# mainboard_teensy41.net
KiCad netlist of a schematic drawn in EAGLE
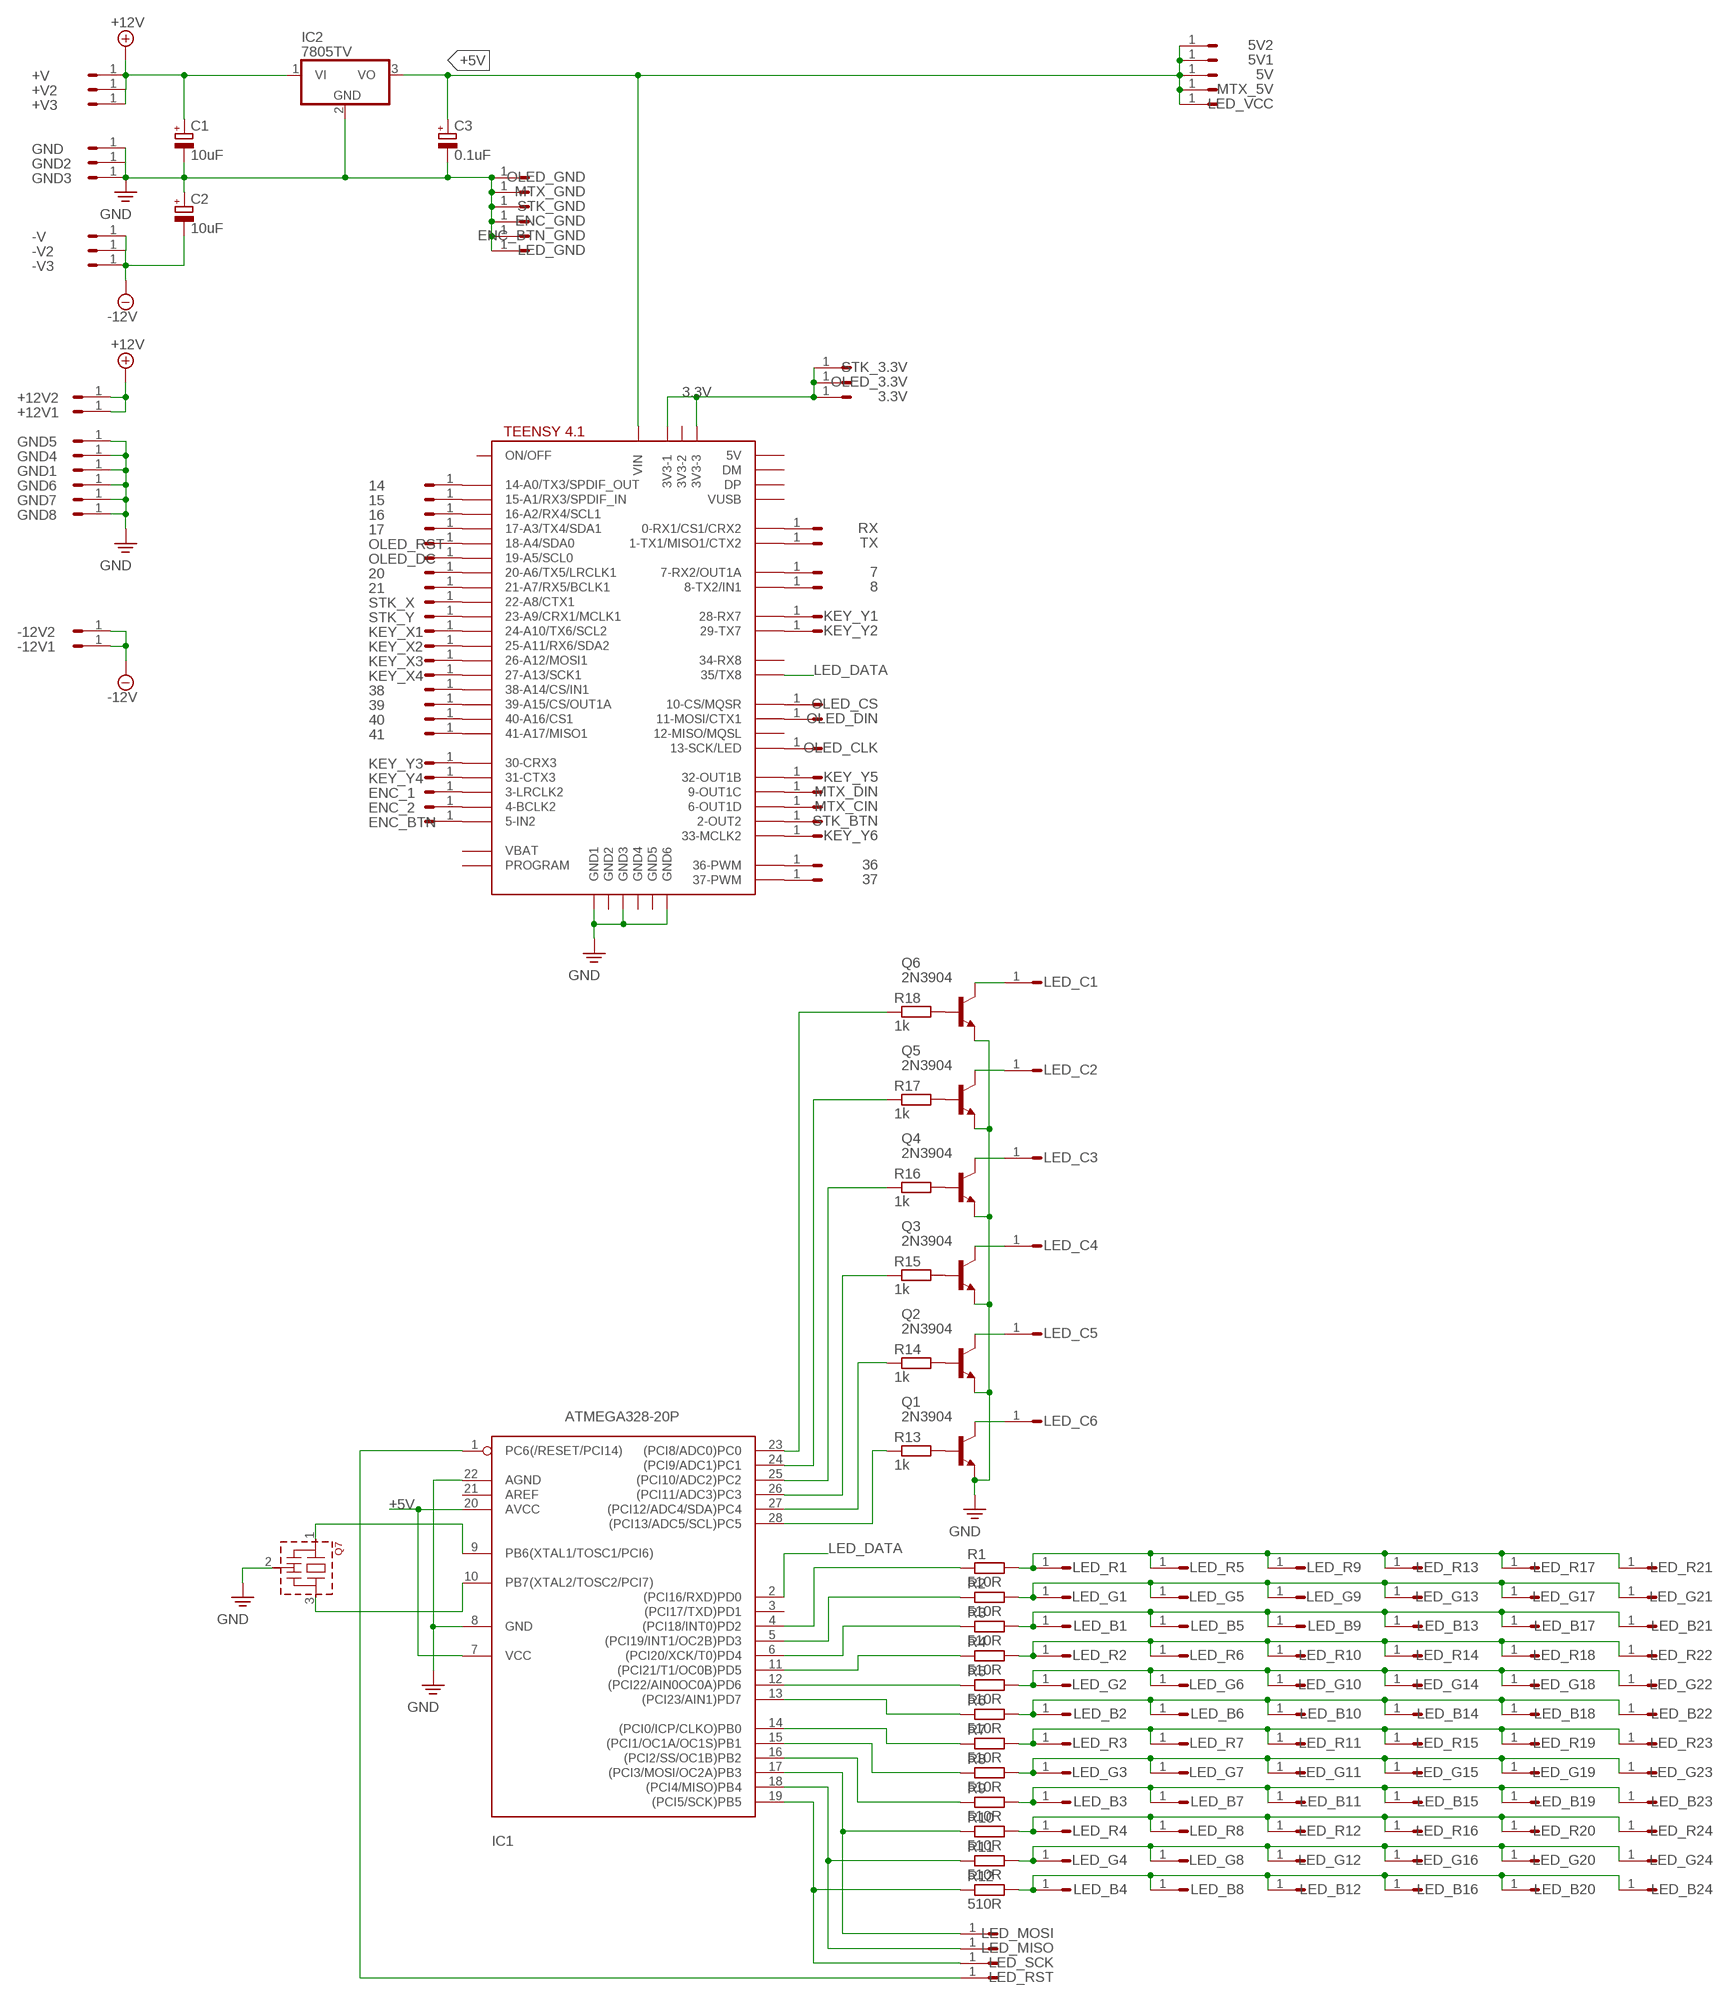
[diagram p0: schematic, sheet 1]

(export (version "E")
  (design (tool "Eeschema 10.0.6"))
  (components
    (comp (ref "+12V1")
      (value "HEADER/MALE/01")
      (footprint "eagle-import:HEADER_MALE_01")
      (fields (field (name "SPICEPREFIX") "X"))
      (libsource (lib "eagle-import") (part "HEADER/MALE/01"))
    )
    (comp (ref "+12V2")
      (value "HEADER/MALE/01")
      (footprint "eagle-import:HEADER_MALE_01")
      (fields (field (name "SPICEPREFIX") "X"))
      (libsource (lib "eagle-import") (part "HEADER/MALE/01"))
    )
    (comp (ref "+V")
      (value "HEADER/MALE/01")
      (footprint "eagle-import:HEADER_MALE_01")
      (fields (field (name "SPICEPREFIX") "X"))
      (libsource (lib "eagle-import") (part "HEADER/MALE/01"))
    )
    (comp (ref "+V2")
      (value "HEADER/MALE/01")
      (footprint "eagle-import:HEADER_MALE_01")
      (fields (field (name "SPICEPREFIX") "X"))
      (libsource (lib "eagle-import") (part "HEADER/MALE/01"))
    )
    (comp (ref "+V3")
      (value "HEADER/MALE/01")
      (footprint "eagle-import:HEADER_MALE_01")
      (fields (field (name "SPICEPREFIX") "X"))
      (libsource (lib "eagle-import") (part "HEADER/MALE/01"))
    )
    (comp (ref "-12V1")
      (value "HEADER/MALE/01")
      (footprint "eagle-import:HEADER_MALE_01")
      (fields (field (name "SPICEPREFIX") "X"))
      (libsource (lib "eagle-import") (part "HEADER/MALE/01"))
    )
    (comp (ref "-12V2")
      (value "HEADER/MALE/01")
      (footprint "eagle-import:HEADER_MALE_01")
      (fields (field (name "SPICEPREFIX") "X"))
      (libsource (lib "eagle-import") (part "HEADER/MALE/01"))
    )
    (comp (ref "-V")
      (value "HEADER/MALE/01")
      (footprint "eagle-import:HEADER_MALE_01")
      (fields (field (name "SPICEPREFIX") "X"))
      (libsource (lib "eagle-import") (part "HEADER/MALE/01"))
    )
    (comp (ref "-V2")
      (value "HEADER/MALE/01")
      (footprint "eagle-import:HEADER_MALE_01")
      (fields (field (name "SPICEPREFIX") "X"))
      (libsource (lib "eagle-import") (part "HEADER/MALE/01"))
    )
    (comp (ref "-V3")
      (value "HEADER/MALE/01")
      (footprint "eagle-import:HEADER_MALE_01")
      (fields (field (name "SPICEPREFIX") "X"))
      (libsource (lib "eagle-import") (part "HEADER/MALE/01"))
    )
    (comp (ref "3.3V")
      (value "HEADER/MALE/01")
      (footprint "eagle-import:HEADER_MALE_01")
      (fields (field (name "SPICEPREFIX") "X"))
      (libsource (lib "eagle-import") (part "HEADER/MALE/01"))
    )
    (comp (ref "5V")
      (value "HEADER/MALE/01")
      (footprint "eagle-import:HEADER_MALE_01")
      (fields (field (name "SPICEPREFIX") "X"))
      (libsource (lib "eagle-import") (part "HEADER/MALE/01"))
    )
    (comp (ref "5V1")
      (value "HEADER/MALE/01")
      (footprint "eagle-import:HEADER_MALE_01")
      (fields (field (name "SPICEPREFIX") "X"))
      (libsource (lib "eagle-import") (part "HEADER/MALE/01"))
    )
    (comp (ref "5V2")
      (value "HEADER/MALE/01")
      (footprint "eagle-import:HEADER_MALE_01")
      (fields (field (name "SPICEPREFIX") "X"))
      (libsource (lib "eagle-import") (part "HEADER/MALE/01"))
    )
    (comp (ref "7")
      (value "HEADER/MALE/01")
      (footprint "eagle-import:HEADER_MALE_01")
      (fields (field (name "SPICEPREFIX") "X"))
      (libsource (lib "eagle-import") (part "HEADER/MALE/01"))
    )
    (comp (ref "8")
      (value "HEADER/MALE/01")
      (footprint "eagle-import:HEADER_MALE_01")
      (fields (field (name "SPICEPREFIX") "X"))
      (libsource (lib "eagle-import") (part "HEADER/MALE/01"))
    )
    (comp (ref "14")
      (value "HEADER/MALE/01")
      (footprint "eagle-import:HEADER_MALE_01")
      (fields (field (name "SPICEPREFIX") "X"))
      (libsource (lib "eagle-import") (part "HEADER/MALE/01"))
    )
    (comp (ref "15")
      (value "HEADER/MALE/01")
      (footprint "eagle-import:HEADER_MALE_01")
      (fields (field (name "SPICEPREFIX") "X"))
      (libsource (lib "eagle-import") (part "HEADER/MALE/01"))
    )
    (comp (ref "16")
      (value "HEADER/MALE/01")
      (footprint "eagle-import:HEADER_MALE_01")
      (fields (field (name "SPICEPREFIX") "X"))
      (libsource (lib "eagle-import") (part "HEADER/MALE/01"))
    )
    (comp (ref "17")
      (value "HEADER/MALE/01")
      (footprint "eagle-import:HEADER_MALE_01")
      (fields (field (name "SPICEPREFIX") "X"))
      (libsource (lib "eagle-import") (part "HEADER/MALE/01"))
    )
    (comp (ref "20")
      (value "HEADER/MALE/01")
      (footprint "eagle-import:HEADER_MALE_01")
      (fields (field (name "SPICEPREFIX") "X"))
      (libsource (lib "eagle-import") (part "HEADER/MALE/01"))
    )
    (comp (ref "21")
      (value "HEADER/MALE/01")
      (footprint "eagle-import:HEADER_MALE_01")
      (fields (field (name "SPICEPREFIX") "X"))
      (libsource (lib "eagle-import") (part "HEADER/MALE/01"))
    )
    (comp (ref "36")
      (value "HEADER/MALE/01")
      (footprint "eagle-import:HEADER_MALE_01")
      (fields (field (name "SPICEPREFIX") "X"))
      (libsource (lib "eagle-import") (part "HEADER/MALE/01"))
    )
    (comp (ref "37")
      (value "HEADER/MALE/01")
      (footprint "eagle-import:HEADER_MALE_01")
      (fields (field (name "SPICEPREFIX") "X"))
      (libsource (lib "eagle-import") (part "HEADER/MALE/01"))
    )
    (comp (ref "38")
      (value "HEADER/MALE/01")
      (footprint "eagle-import:HEADER_MALE_01")
      (fields (field (name "SPICEPREFIX") "X"))
      (libsource (lib "eagle-import") (part "HEADER/MALE/01"))
    )
    (comp (ref "39")
      (value "HEADER/MALE/01")
      (footprint "eagle-import:HEADER_MALE_01")
      (fields (field (name "SPICEPREFIX") "X"))
      (libsource (lib "eagle-import") (part "HEADER/MALE/01"))
    )
    (comp (ref "40")
      (value "HEADER/MALE/01")
      (footprint "eagle-import:HEADER_MALE_01")
      (fields (field (name "SPICEPREFIX") "X"))
      (libsource (lib "eagle-import") (part "HEADER/MALE/01"))
    )
    (comp (ref "41")
      (value "HEADER/MALE/01")
      (footprint "eagle-import:HEADER_MALE_01")
      (fields (field (name "SPICEPREFIX") "X"))
      (libsource (lib "eagle-import") (part "HEADER/MALE/01"))
    )
    (comp (ref "C1")
      (value "10uF")
      (footprint "eagle-import:E2,5-6")
      (fields (field (name "SPICEPREFIX") "C"))
      (libsource (lib "eagle-import") (part "CAPACITOR/POLARIZEDE2.5-6"))
    )
    (comp (ref "C2")
      (value "10uF")
      (footprint "eagle-import:E2,5-6")
      (fields (field (name "SPICEPREFIX") "C"))
      (libsource (lib "eagle-import") (part "CAPACITOR/POLARIZEDE2.5-6"))
    )
    (comp (ref "C3")
      (value "0.1uF")
      (footprint "eagle-import:E2,5-6")
      (fields (field (name "SPICEPREFIX") "C"))
      (libsource (lib "eagle-import") (part "CAPACITOR/POLARIZEDE2.5-6"))
    )
    (comp (ref "ENC_1")
      (value "HEADER/MALE/01")
      (footprint "eagle-import:HEADER_MALE_01")
      (fields (field (name "SPICEPREFIX") "X"))
      (libsource (lib "eagle-import") (part "HEADER/MALE/01"))
    )
    (comp (ref "ENC_2")
      (value "HEADER/MALE/01")
      (footprint "eagle-import:HEADER_MALE_01")
      (fields (field (name "SPICEPREFIX") "X"))
      (libsource (lib "eagle-import") (part "HEADER/MALE/01"))
    )
    (comp (ref "ENC_BTN")
      (value "HEADER/MALE/01")
      (footprint "eagle-import:HEADER_MALE_01")
      (fields (field (name "SPICEPREFIX") "X"))
      (libsource (lib "eagle-import") (part "HEADER/MALE/01"))
    )
    (comp (ref "ENC_BTN_GND")
      (value "HEADER/MALE/01")
      (footprint "eagle-import:HEADER_MALE_01")
      (fields (field (name "SPICEPREFIX") "X"))
      (libsource (lib "eagle-import") (part "HEADER/MALE/01"))
    )
    (comp (ref "ENC_GND")
      (value "HEADER/MALE/01")
      (footprint "eagle-import:HEADER_MALE_01")
      (fields (field (name "SPICEPREFIX") "X"))
      (libsource (lib "eagle-import") (part "HEADER/MALE/01"))
    )
    (comp (ref "GND")
      (value "HEADER/MALE/01")
      (footprint "eagle-import:HEADER_MALE_01")
      (fields (field (name "SPICEPREFIX") "X"))
      (libsource (lib "eagle-import") (part "HEADER/MALE/01"))
    )
    (comp (ref "GND1")
      (value "HEADER/MALE/01")
      (footprint "eagle-import:HEADER_MALE_01")
      (fields (field (name "SPICEPREFIX") "X"))
      (libsource (lib "eagle-import") (part "HEADER/MALE/01"))
    )
    (comp (ref "GND2")
      (value "HEADER/MALE/01")
      (footprint "eagle-import:HEADER_MALE_01")
      (fields (field (name "SPICEPREFIX") "X"))
      (libsource (lib "eagle-import") (part "HEADER/MALE/01"))
    )
    (comp (ref "GND3")
      (value "HEADER/MALE/01")
      (footprint "eagle-import:HEADER_MALE_01")
      (fields (field (name "SPICEPREFIX") "X"))
      (libsource (lib "eagle-import") (part "HEADER/MALE/01"))
    )
    (comp (ref "GND4")
      (value "HEADER/MALE/01")
      (footprint "eagle-import:HEADER_MALE_01")
      (fields (field (name "SPICEPREFIX") "X"))
      (libsource (lib "eagle-import") (part "HEADER/MALE/01"))
    )
    (comp (ref "GND5")
      (value "HEADER/MALE/01")
      (footprint "eagle-import:HEADER_MALE_01")
      (fields (field (name "SPICEPREFIX") "X"))
      (libsource (lib "eagle-import") (part "HEADER/MALE/01"))
    )
    (comp (ref "GND6")
      (value "HEADER/MALE/01")
      (footprint "eagle-import:HEADER_MALE_01")
      (fields (field (name "SPICEPREFIX") "X"))
      (libsource (lib "eagle-import") (part "HEADER/MALE/01"))
    )
    (comp (ref "GND7")
      (value "HEADER/MALE/01")
      (footprint "eagle-import:HEADER_MALE_01")
      (fields (field (name "SPICEPREFIX") "X"))
      (libsource (lib "eagle-import") (part "HEADER/MALE/01"))
    )
    (comp (ref "GND8")
      (value "HEADER/MALE/01")
      (footprint "eagle-import:HEADER_MALE_01")
      (fields (field (name "SPICEPREFIX") "X"))
      (libsource (lib "eagle-import") (part "HEADER/MALE/01"))
    )
    (comp (ref "IC1")
      (value "ATMEGA328-20P")
      (footprint "eagle-import:DIL28-3")
      (libsource (lib "eagle-import") (part "ATMEGA328P-20"))
    )
    (comp (ref "IC2")
      (value "7805TV")
      (footprint "eagle-import:TO220V")
      (libsource (lib "eagle-import") (part "78TV05"))
    )
    (comp (ref "KEY_X1")
      (value "HEADER/MALE/01")
      (footprint "eagle-import:HEADER_MALE_01")
      (fields (field (name "SPICEPREFIX") "X"))
      (libsource (lib "eagle-import") (part "HEADER/MALE/01"))
    )
    (comp (ref "KEY_X2")
      (value "HEADER/MALE/01")
      (footprint "eagle-import:HEADER_MALE_01")
      (fields (field (name "SPICEPREFIX") "X"))
      (libsource (lib "eagle-import") (part "HEADER/MALE/01"))
    )
    (comp (ref "KEY_X3")
      (value "HEADER/MALE/01")
      (footprint "eagle-import:HEADER_MALE_01")
      (fields (field (name "SPICEPREFIX") "X"))
      (libsource (lib "eagle-import") (part "HEADER/MALE/01"))
    )
    (comp (ref "KEY_X4")
      (value "HEADER/MALE/01")
      (footprint "eagle-import:HEADER_MALE_01")
      (fields (field (name "SPICEPREFIX") "X"))
      (libsource (lib "eagle-import") (part "HEADER/MALE/01"))
    )
    (comp (ref "KEY_Y1")
      (value "HEADER/MALE/01")
      (footprint "eagle-import:HEADER_MALE_01")
      (fields (field (name "SPICEPREFIX") "X"))
      (libsource (lib "eagle-import") (part "HEADER/MALE/01"))
    )
    (comp (ref "KEY_Y2")
      (value "HEADER/MALE/01")
      (footprint "eagle-import:HEADER_MALE_01")
      (fields (field (name "SPICEPREFIX") "X"))
      (libsource (lib "eagle-import") (part "HEADER/MALE/01"))
    )
    (comp (ref "KEY_Y3")
      (value "HEADER/MALE/01")
      (footprint "eagle-import:HEADER_MALE_01")
      (fields (field (name "SPICEPREFIX") "X"))
      (libsource (lib "eagle-import") (part "HEADER/MALE/01"))
    )
    (comp (ref "KEY_Y4")
      (value "HEADER/MALE/01")
      (footprint "eagle-import:HEADER_MALE_01")
      (fields (field (name "SPICEPREFIX") "X"))
      (libsource (lib "eagle-import") (part "HEADER/MALE/01"))
    )
    (comp (ref "KEY_Y5")
      (value "HEADER/MALE/01")
      (footprint "eagle-import:HEADER_MALE_01")
      (fields (field (name "SPICEPREFIX") "X"))
      (libsource (lib "eagle-import") (part "HEADER/MALE/01"))
    )
    (comp (ref "KEY_Y6")
      (value "HEADER/MALE/01")
      (footprint "eagle-import:HEADER_MALE_01")
      (fields (field (name "SPICEPREFIX") "X"))
      (libsource (lib "eagle-import") (part "HEADER/MALE/01"))
    )
    (comp (ref "LED_B1")
      (value "HEADER/MALE/01")
      (footprint "eagle-import:HEADER_MALE_01")
      (fields (field (name "SPICEPREFIX") "X"))
      (libsource (lib "eagle-import") (part "HEADER/MALE/01"))
    )
    (comp (ref "LED_B2")
      (value "HEADER/MALE/01")
      (footprint "eagle-import:HEADER_MALE_01")
      (fields (field (name "SPICEPREFIX") "X"))
      (libsource (lib "eagle-import") (part "HEADER/MALE/01"))
    )
    (comp (ref "LED_B3")
      (value "HEADER/MALE/01")
      (footprint "eagle-import:HEADER_MALE_01")
      (fields (field (name "SPICEPREFIX") "X"))
      (libsource (lib "eagle-import") (part "HEADER/MALE/01"))
    )
    (comp (ref "LED_B4")
      (value "HEADER/MALE/01")
      (footprint "eagle-import:HEADER_MALE_01")
      (fields (field (name "SPICEPREFIX") "X"))
      (libsource (lib "eagle-import") (part "HEADER/MALE/01"))
    )
    (comp (ref "LED_B5")
      (value "HEADER/MALE/01")
      (footprint "eagle-import:HEADER_MALE_01")
      (fields (field (name "SPICEPREFIX") "X"))
      (libsource (lib "eagle-import") (part "HEADER/MALE/01"))
    )
    (comp (ref "LED_B6")
      (value "HEADER/MALE/01")
      (footprint "eagle-import:HEADER_MALE_01")
      (fields (field (name "SPICEPREFIX") "X"))
      (libsource (lib "eagle-import") (part "HEADER/MALE/01"))
    )
    (comp (ref "LED_B7")
      (value "HEADER/MALE/01")
      (footprint "eagle-import:HEADER_MALE_01")
      (fields (field (name "SPICEPREFIX") "X"))
      (libsource (lib "eagle-import") (part "HEADER/MALE/01"))
    )
    (comp (ref "LED_B8")
      (value "HEADER/MALE/01")
      (footprint "eagle-import:HEADER_MALE_01")
      (fields (field (name "SPICEPREFIX") "X"))
      (libsource (lib "eagle-import") (part "HEADER/MALE/01"))
    )
    (comp (ref "LED_B9")
      (value "HEADER/MALE/01")
      (footprint "eagle-import:HEADER_MALE_01")
      (fields (field (name "SPICEPREFIX") "X"))
      (libsource (lib "eagle-import") (part "HEADER/MALE/01"))
    )
    (comp (ref "LED_B10")
      (value "HEADER/MALE/01")
      (footprint "eagle-import:HEADER_MALE_01")
      (fields (field (name "SPICEPREFIX") "X"))
      (libsource (lib "eagle-import") (part "HEADER/MALE/01"))
    )
    (comp (ref "LED_B11")
      (value "HEADER/MALE/01")
      (footprint "eagle-import:HEADER_MALE_01")
      (fields (field (name "SPICEPREFIX") "X"))
      (libsource (lib "eagle-import") (part "HEADER/MALE/01"))
    )
    (comp (ref "LED_B12")
      (value "HEADER/MALE/01")
      (footprint "eagle-import:HEADER_MALE_01")
      (fields (field (name "SPICEPREFIX") "X"))
      (libsource (lib "eagle-import") (part "HEADER/MALE/01"))
    )
    (comp (ref "LED_B13")
      (value "HEADER/MALE/01")
      (footprint "eagle-import:HEADER_MALE_01")
      (fields (field (name "SPICEPREFIX") "X"))
      (libsource (lib "eagle-import") (part "HEADER/MALE/01"))
    )
    (comp (ref "LED_B14")
      (value "HEADER/MALE/01")
      (footprint "eagle-import:HEADER_MALE_01")
      (fields (field (name "SPICEPREFIX") "X"))
      (libsource (lib "eagle-import") (part "HEADER/MALE/01"))
    )
    (comp (ref "LED_B15")
      (value "HEADER/MALE/01")
      (footprint "eagle-import:HEADER_MALE_01")
      (fields (field (name "SPICEPREFIX") "X"))
      (libsource (lib "eagle-import") (part "HEADER/MALE/01"))
    )
    (comp (ref "LED_B16")
      (value "HEADER/MALE/01")
      (footprint "eagle-import:HEADER_MALE_01")
      (fields (field (name "SPICEPREFIX") "X"))
      (libsource (lib "eagle-import") (part "HEADER/MALE/01"))
    )
    (comp (ref "LED_B17")
      (value "HEADER/MALE/01")
      (footprint "eagle-import:HEADER_MALE_01")
      (fields (field (name "SPICEPREFIX") "X"))
      (libsource (lib "eagle-import") (part "HEADER/MALE/01"))
    )
    (comp (ref "LED_B18")
      (value "HEADER/MALE/01")
      (footprint "eagle-import:HEADER_MALE_01")
      (fields (field (name "SPICEPREFIX") "X"))
      (libsource (lib "eagle-import") (part "HEADER/MALE/01"))
    )
    (comp (ref "LED_B19")
      (value "HEADER/MALE/01")
      (footprint "eagle-import:HEADER_MALE_01")
      (fields (field (name "SPICEPREFIX") "X"))
      (libsource (lib "eagle-import") (part "HEADER/MALE/01"))
    )
    (comp (ref "LED_B20")
      (value "HEADER/MALE/01")
      (footprint "eagle-import:HEADER_MALE_01")
      (fields (field (name "SPICEPREFIX") "X"))
      (libsource (lib "eagle-import") (part "HEADER/MALE/01"))
    )
    (comp (ref "LED_B21")
      (value "HEADER/MALE/01")
      (footprint "eagle-import:HEADER_MALE_01")
      (fields (field (name "SPICEPREFIX") "X"))
      (libsource (lib "eagle-import") (part "HEADER/MALE/01"))
    )
    (comp (ref "LED_B22")
      (value "HEADER/MALE/01")
      (footprint "eagle-import:HEADER_MALE_01")
      (fields (field (name "SPICEPREFIX") "X"))
      (libsource (lib "eagle-import") (part "HEADER/MALE/01"))
    )
    (comp (ref "LED_B23")
      (value "HEADER/MALE/01")
      (footprint "eagle-import:HEADER_MALE_01")
      (fields (field (name "SPICEPREFIX") "X"))
      (libsource (lib "eagle-import") (part "HEADER/MALE/01"))
    )
    (comp (ref "LED_B24")
      (value "HEADER/MALE/01")
      (footprint "eagle-import:HEADER_MALE_01")
      (fields (field (name "SPICEPREFIX") "X"))
      (libsource (lib "eagle-import") (part "HEADER/MALE/01"))
    )
    (comp (ref "LED_C1")
      (value "HEADER/MALE/01")
      (footprint "eagle-import:HEADER_MALE_01")
      (fields (field (name "SPICEPREFIX") "X"))
      (libsource (lib "eagle-import") (part "HEADER/MALE/01"))
    )
    (comp (ref "LED_C2")
      (value "HEADER/MALE/01")
      (footprint "eagle-import:HEADER_MALE_01")
      (fields (field (name "SPICEPREFIX") "X"))
      (libsource (lib "eagle-import") (part "HEADER/MALE/01"))
    )
    (comp (ref "LED_C3")
      (value "HEADER/MALE/01")
      (footprint "eagle-import:HEADER_MALE_01")
      (fields (field (name "SPICEPREFIX") "X"))
      (libsource (lib "eagle-import") (part "HEADER/MALE/01"))
    )
    (comp (ref "LED_C4")
      (value "HEADER/MALE/01")
      (footprint "eagle-import:HEADER_MALE_01")
      (fields (field (name "SPICEPREFIX") "X"))
      (libsource (lib "eagle-import") (part "HEADER/MALE/01"))
    )
    (comp (ref "LED_C5")
      (value "HEADER/MALE/01")
      (footprint "eagle-import:HEADER_MALE_01")
      (fields (field (name "SPICEPREFIX") "X"))
      (libsource (lib "eagle-import") (part "HEADER/MALE/01"))
    )
    (comp (ref "LED_C6")
      (value "HEADER/MALE/01")
      (footprint "eagle-import:HEADER_MALE_01")
      (fields (field (name "SPICEPREFIX") "X"))
      (libsource (lib "eagle-import") (part "HEADER/MALE/01"))
    )
    (comp (ref "LED_G1")
      (value "HEADER/MALE/01")
      (footprint "eagle-import:HEADER_MALE_01")
      (fields (field (name "SPICEPREFIX") "X"))
      (libsource (lib "eagle-import") (part "HEADER/MALE/01"))
    )
    (comp (ref "LED_G2")
      (value "HEADER/MALE/01")
      (footprint "eagle-import:HEADER_MALE_01")
      (fields (field (name "SPICEPREFIX") "X"))
      (libsource (lib "eagle-import") (part "HEADER/MALE/01"))
    )
    (comp (ref "LED_G3")
      (value "HEADER/MALE/01")
      (footprint "eagle-import:HEADER_MALE_01")
      (fields (field (name "SPICEPREFIX") "X"))
      (libsource (lib "eagle-import") (part "HEADER/MALE/01"))
    )
    (comp (ref "LED_G4")
      (value "HEADER/MALE/01")
      (footprint "eagle-import:HEADER_MALE_01")
      (fields (field (name "SPICEPREFIX") "X"))
      (libsource (lib "eagle-import") (part "HEADER/MALE/01"))
    )
    (comp (ref "LED_G5")
      (value "HEADER/MALE/01")
      (footprint "eagle-import:HEADER_MALE_01")
      (fields (field (name "SPICEPREFIX") "X"))
      (libsource (lib "eagle-import") (part "HEADER/MALE/01"))
    )
    (comp (ref "LED_G6")
      (value "HEADER/MALE/01")
      (footprint "eagle-import:HEADER_MALE_01")
      (fields (field (name "SPICEPREFIX") "X"))
      (libsource (lib "eagle-import") (part "HEADER/MALE/01"))
    )
    (comp (ref "LED_G7")
      (value "HEADER/MALE/01")
      (footprint "eagle-import:HEADER_MALE_01")
      (fields (field (name "SPICEPREFIX") "X"))
      (libsource (lib "eagle-import") (part "HEADER/MALE/01"))
    )
    (comp (ref "LED_G8")
      (value "HEADER/MALE/01")
      (footprint "eagle-import:HEADER_MALE_01")
      (fields (field (name "SPICEPREFIX") "X"))
      (libsource (lib "eagle-import") (part "HEADER/MALE/01"))
    )
    (comp (ref "LED_G9")
      (value "HEADER/MALE/01")
      (footprint "eagle-import:HEADER_MALE_01")
      (fields (field (name "SPICEPREFIX") "X"))
      (libsource (lib "eagle-import") (part "HEADER/MALE/01"))
    )
    (comp (ref "LED_G10")
      (value "HEADER/MALE/01")
      (footprint "eagle-import:HEADER_MALE_01")
      (fields (field (name "SPICEPREFIX") "X"))
      (libsource (lib "eagle-import") (part "HEADER/MALE/01"))
    )
    (comp (ref "LED_G11")
      (value "HEADER/MALE/01")
      (footprint "eagle-import:HEADER_MALE_01")
      (fields (field (name "SPICEPREFIX") "X"))
      (libsource (lib "eagle-import") (part "HEADER/MALE/01"))
    )
    (comp (ref "LED_G12")
      (value "HEADER/MALE/01")
      (footprint "eagle-import:HEADER_MALE_01")
      (fields (field (name "SPICEPREFIX") "X"))
      (libsource (lib "eagle-import") (part "HEADER/MALE/01"))
    )
    (comp (ref "LED_G13")
      (value "HEADER/MALE/01")
      (footprint "eagle-import:HEADER_MALE_01")
      (fields (field (name "SPICEPREFIX") "X"))
      (libsource (lib "eagle-import") (part "HEADER/MALE/01"))
    )
    (comp (ref "LED_G14")
      (value "HEADER/MALE/01")
      (footprint "eagle-import:HEADER_MALE_01")
      (fields (field (name "SPICEPREFIX") "X"))
      (libsource (lib "eagle-import") (part "HEADER/MALE/01"))
    )
    (comp (ref "LED_G15")
      (value "HEADER/MALE/01")
      (footprint "eagle-import:HEADER_MALE_01")
      (fields (field (name "SPICEPREFIX") "X"))
      (libsource (lib "eagle-import") (part "HEADER/MALE/01"))
    )
    (comp (ref "LED_G16")
      (value "HEADER/MALE/01")
      (footprint "eagle-import:HEADER_MALE_01")
      (fields (field (name "SPICEPREFIX") "X"))
      (libsource (lib "eagle-import") (part "HEADER/MALE/01"))
    )
    (comp (ref "LED_G17")
      (value "HEADER/MALE/01")
      (footprint "eagle-import:HEADER_MALE_01")
      (fields (field (name "SPICEPREFIX") "X"))
      (libsource (lib "eagle-import") (part "HEADER/MALE/01"))
    )
    (comp (ref "LED_G18")
      (value "HEADER/MALE/01")
      (footprint "eagle-import:HEADER_MALE_01")
      (fields (field (name "SPICEPREFIX") "X"))
      (libsource (lib "eagle-import") (part "HEADER/MALE/01"))
    )
    (comp (ref "LED_G19")
      (value "HEADER/MALE/01")
      (footprint "eagle-import:HEADER_MALE_01")
      (fields (field (name "SPICEPREFIX") "X"))
      (libsource (lib "eagle-import") (part "HEADER/MALE/01"))
    )
    (comp (ref "LED_G20")
      (value "HEADER/MALE/01")
      (footprint "eagle-import:HEADER_MALE_01")
      (fields (field (name "SPICEPREFIX") "X"))
      (libsource (lib "eagle-import") (part "HEADER/MALE/01"))
    )
    (comp (ref "LED_G21")
      (value "HEADER/MALE/01")
      (footprint "eagle-import:HEADER_MALE_01")
      (fields (field (name "SPICEPREFIX") "X"))
      (libsource (lib "eagle-import") (part "HEADER/MALE/01"))
    )
    (comp (ref "LED_G22")
      (value "HEADER/MALE/01")
      (footprint "eagle-import:HEADER_MALE_01")
      (fields (field (name "SPICEPREFIX") "X"))
      (libsource (lib "eagle-import") (part "HEADER/MALE/01"))
    )
    (comp (ref "LED_G23")
      (value "HEADER/MALE/01")
      (footprint "eagle-import:HEADER_MALE_01")
      (fields (field (name "SPICEPREFIX") "X"))
      (libsource (lib "eagle-import") (part "HEADER/MALE/01"))
    )
    (comp (ref "LED_G24")
      (value "HEADER/MALE/01")
      (footprint "eagle-import:HEADER_MALE_01")
      (fields (field (name "SPICEPREFIX") "X"))
      (libsource (lib "eagle-import") (part "HEADER/MALE/01"))
    )
    (comp (ref "LED_GND")
      (value "HEADER/MALE/01")
      (footprint "eagle-import:HEADER_MALE_01")
      (fields (field (name "SPICEPREFIX") "X"))
      (libsource (lib "eagle-import") (part "HEADER/MALE/01"))
    )
    (comp (ref "LED_MISO")
      (value "HEADER/MALE/01")
      (footprint "eagle-import:HEADER_MALE_01")
      (fields (field (name "SPICEPREFIX") "X"))
      (libsource (lib "eagle-import") (part "HEADER/MALE/01"))
    )
    (comp (ref "LED_MOSI")
      (value "HEADER/MALE/01")
      (footprint "eagle-import:HEADER_MALE_01")
      (fields (field (name "SPICEPREFIX") "X"))
      (libsource (lib "eagle-import") (part "HEADER/MALE/01"))
    )
    (comp (ref "LED_R1")
      (value "HEADER/MALE/01")
      (footprint "eagle-import:HEADER_MALE_01")
      (fields (field (name "SPICEPREFIX") "X"))
      (libsource (lib "eagle-import") (part "HEADER/MALE/01"))
    )
    (comp (ref "LED_R2")
      (value "HEADER/MALE/01")
      (footprint "eagle-import:HEADER_MALE_01")
      (fields (field (name "SPICEPREFIX") "X"))
      (libsource (lib "eagle-import") (part "HEADER/MALE/01"))
    )
    (comp (ref "LED_R3")
      (value "HEADER/MALE/01")
      (footprint "eagle-import:HEADER_MALE_01")
      (fields (field (name "SPICEPREFIX") "X"))
      (libsource (lib "eagle-import") (part "HEADER/MALE/01"))
    )
    (comp (ref "LED_R4")
      (value "HEADER/MALE/01")
      (footprint "eagle-import:HEADER_MALE_01")
      (fields (field (name "SPICEPREFIX") "X"))
      (libsource (lib "eagle-import") (part "HEADER/MALE/01"))
    )
    (comp (ref "LED_R5")
      (value "HEADER/MALE/01")
      (footprint "eagle-import:HEADER_MALE_01")
      (fields (field (name "SPICEPREFIX") "X"))
      (libsource (lib "eagle-import") (part "HEADER/MALE/01"))
    )
    (comp (ref "LED_R6")
      (value "HEADER/MALE/01")
      (footprint "eagle-import:HEADER_MALE_01")
      (fields (field (name "SPICEPREFIX") "X"))
      (libsource (lib "eagle-import") (part "HEADER/MALE/01"))
    )
    (comp (ref "LED_R7")
      (value "HEADER/MALE/01")
      (footprint "eagle-import:HEADER_MALE_01")
      (fields (field (name "SPICEPREFIX") "X"))
      (libsource (lib "eagle-import") (part "HEADER/MALE/01"))
    )
    (comp (ref "LED_R8")
      (value "HEADER/MALE/01")
      (footprint "eagle-import:HEADER_MALE_01")
      (fields (field (name "SPICEPREFIX") "X"))
      (libsource (lib "eagle-import") (part "HEADER/MALE/01"))
    )
    (comp (ref "LED_R9")
      (value "HEADER/MALE/01")
      (footprint "eagle-import:HEADER_MALE_01")
      (fields (field (name "SPICEPREFIX") "X"))
      (libsource (lib "eagle-import") (part "HEADER/MALE/01"))
    )
    (comp (ref "LED_R10")
      (value "HEADER/MALE/01")
      (footprint "eagle-import:HEADER_MALE_01")
      (fields (field (name "SPICEPREFIX") "X"))
      (libsource (lib "eagle-import") (part "HEADER/MALE/01"))
    )
    (comp (ref "LED_R11")
      (value "HEADER/MALE/01")
      (footprint "eagle-import:HEADER_MALE_01")
      (fields (field (name "SPICEPREFIX") "X"))
      (libsource (lib "eagle-import") (part "HEADER/MALE/01"))
    )
    (comp (ref "LED_R12")
      (value "HEADER/MALE/01")
      (footprint "eagle-import:HEADER_MALE_01")
      (fields (field (name "SPICEPREFIX") "X"))
      (libsource (lib "eagle-import") (part "HEADER/MALE/01"))
    )
    (comp (ref "LED_R13")
      (value "HEADER/MALE/01")
      (footprint "eagle-import:HEADER_MALE_01")
      (fields (field (name "SPICEPREFIX") "X"))
      (libsource (lib "eagle-import") (part "HEADER/MALE/01"))
    )
    (comp (ref "LED_R14")
      (value "HEADER/MALE/01")
      (footprint "eagle-import:HEADER_MALE_01")
      (fields (field (name "SPICEPREFIX") "X"))
      (libsource (lib "eagle-import") (part "HEADER/MALE/01"))
    )
    (comp (ref "LED_R15")
      (value "HEADER/MALE/01")
      (footprint "eagle-import:HEADER_MALE_01")
      (fields (field (name "SPICEPREFIX") "X"))
      (libsource (lib "eagle-import") (part "HEADER/MALE/01"))
    )
    (comp (ref "LED_R16")
      (value "HEADER/MALE/01")
      (footprint "eagle-import:HEADER_MALE_01")
      (fields (field (name "SPICEPREFIX") "X"))
      (libsource (lib "eagle-import") (part "HEADER/MALE/01"))
    )
    (comp (ref "LED_R17")
      (value "HEADER/MALE/01")
      (footprint "eagle-import:HEADER_MALE_01")
      (fields (field (name "SPICEPREFIX") "X"))
      (libsource (lib "eagle-import") (part "HEADER/MALE/01"))
    )
    (comp (ref "LED_R18")
      (value "HEADER/MALE/01")
      (footprint "eagle-import:HEADER_MALE_01")
      (fields (field (name "SPICEPREFIX") "X"))
      (libsource (lib "eagle-import") (part "HEADER/MALE/01"))
    )
    (comp (ref "LED_R19")
      (value "HEADER/MALE/01")
      (footprint "eagle-import:HEADER_MALE_01")
      (fields (field (name "SPICEPREFIX") "X"))
      (libsource (lib "eagle-import") (part "HEADER/MALE/01"))
    )
    (comp (ref "LED_R20")
      (value "HEADER/MALE/01")
      (footprint "eagle-import:HEADER_MALE_01")
      (fields (field (name "SPICEPREFIX") "X"))
      (libsource (lib "eagle-import") (part "HEADER/MALE/01"))
    )
    (comp (ref "LED_R21")
      (value "HEADER/MALE/01")
      (footprint "eagle-import:HEADER_MALE_01")
      (fields (field (name "SPICEPREFIX") "X"))
      (libsource (lib "eagle-import") (part "HEADER/MALE/01"))
    )
    (comp (ref "LED_R22")
      (value "HEADER/MALE/01")
      (footprint "eagle-import:HEADER_MALE_01")
      (fields (field (name "SPICEPREFIX") "X"))
      (libsource (lib "eagle-import") (part "HEADER/MALE/01"))
    )
    (comp (ref "LED_R23")
      (value "HEADER/MALE/01")
      (footprint "eagle-import:HEADER_MALE_01")
      (fields (field (name "SPICEPREFIX") "X"))
      (libsource (lib "eagle-import") (part "HEADER/MALE/01"))
    )
    (comp (ref "LED_R24")
      (value "HEADER/MALE/01")
      (footprint "eagle-import:HEADER_MALE_01")
      (fields (field (name "SPICEPREFIX") "X"))
      (libsource (lib "eagle-import") (part "HEADER/MALE/01"))
    )
    (comp (ref "LED_RST")
      (value "HEADER/MALE/01")
      (footprint "eagle-import:HEADER_MALE_01")
      (fields (field (name "SPICEPREFIX") "X"))
      (libsource (lib "eagle-import") (part "HEADER/MALE/01"))
    )
    (comp (ref "LED_SCK")
      (value "HEADER/MALE/01")
      (footprint "eagle-import:HEADER_MALE_01")
      (fields (field (name "SPICEPREFIX") "X"))
      (libsource (lib "eagle-import") (part "HEADER/MALE/01"))
    )
    (comp (ref "LED_VCC")
      (value "HEADER/MALE/01")
      (footprint "eagle-import:HEADER_MALE_01")
      (fields (field (name "SPICEPREFIX") "X"))
      (libsource (lib "eagle-import") (part "HEADER/MALE/01"))
    )
    (comp (ref "MTX_5V")
      (value "HEADER/MALE/01")
      (footprint "eagle-import:HEADER_MALE_01")
      (fields (field (name "SPICEPREFIX") "X"))
      (libsource (lib "eagle-import") (part "HEADER/MALE/01"))
    )
    (comp (ref "MTX_CIN")
      (value "HEADER/MALE/01")
      (footprint "eagle-import:HEADER_MALE_01")
      (fields (field (name "SPICEPREFIX") "X"))
      (libsource (lib "eagle-import") (part "HEADER/MALE/01"))
    )
    (comp (ref "MTX_DIN")
      (value "HEADER/MALE/01")
      (footprint "eagle-import:HEADER_MALE_01")
      (fields (field (name "SPICEPREFIX") "X"))
      (libsource (lib "eagle-import") (part "HEADER/MALE/01"))
    )
    (comp (ref "MTX_GND")
      (value "HEADER/MALE/01")
      (footprint "eagle-import:HEADER_MALE_01")
      (fields (field (name "SPICEPREFIX") "X"))
      (libsource (lib "eagle-import") (part "HEADER/MALE/01"))
    )
    (comp (ref "OLED_3.3V")
      (value "HEADER/MALE/01")
      (footprint "eagle-import:HEADER_MALE_01")
      (fields (field (name "SPICEPREFIX") "X"))
      (libsource (lib "eagle-import") (part "HEADER/MALE/01"))
    )
    (comp (ref "OLED_CLK")
      (value "HEADER/MALE/01")
      (footprint "eagle-import:HEADER_MALE_01")
      (fields (field (name "SPICEPREFIX") "X"))
      (libsource (lib "eagle-import") (part "HEADER/MALE/01"))
    )
    (comp (ref "OLED_CS")
      (value "HEADER/MALE/01")
      (footprint "eagle-import:HEADER_MALE_01")
      (fields (field (name "SPICEPREFIX") "X"))
      (libsource (lib "eagle-import") (part "HEADER/MALE/01"))
    )
    (comp (ref "OLED_DC")
      (value "HEADER/MALE/01")
      (footprint "eagle-import:HEADER_MALE_01")
      (fields (field (name "SPICEPREFIX") "X"))
      (libsource (lib "eagle-import") (part "HEADER/MALE/01"))
    )
    (comp (ref "OLED_DIN")
      (value "HEADER/MALE/01")
      (footprint "eagle-import:HEADER_MALE_01")
      (fields (field (name "SPICEPREFIX") "X"))
      (libsource (lib "eagle-import") (part "HEADER/MALE/01"))
    )
    (comp (ref "OLED_GND")
      (value "HEADER/MALE/01")
      (footprint "eagle-import:HEADER_MALE_01")
      (fields (field (name "SPICEPREFIX") "X"))
      (libsource (lib "eagle-import") (part "HEADER/MALE/01"))
    )
    (comp (ref "OLED_RST")
      (value "HEADER/MALE/01")
      (footprint "eagle-import:HEADER_MALE_01")
      (fields (field (name "SPICEPREFIX") "X"))
      (libsource (lib "eagle-import") (part "HEADER/MALE/01"))
    )
    (comp (ref "Q1")
      (value "2N3904")
      (footprint "eagle-import:TO92")
      (libsource (lib "eagle-import") (part "2N3904"))
    )
    (comp (ref "Q2")
      (value "2N3904")
      (footprint "eagle-import:TO92")
      (libsource (lib "eagle-import") (part "2N3904"))
    )
    (comp (ref "Q3")
      (value "2N3904")
      (footprint "eagle-import:TO92")
      (libsource (lib "eagle-import") (part "2N3904"))
    )
    (comp (ref "Q4")
      (value "2N3904")
      (footprint "eagle-import:TO92")
      (libsource (lib "eagle-import") (part "2N3904"))
    )
    (comp (ref "Q5")
      (value "2N3904")
      (footprint "eagle-import:TO92")
      (libsource (lib "eagle-import") (part "2N3904"))
    )
    (comp (ref "Q6")
      (value "2N3904")
      (footprint "eagle-import:TO92")
      (libsource (lib "eagle-import") (part "2N3904"))
    )
    (comp (ref "Q7")
      (value "CSTLS_G")
      (footprint "eagle-import:CSTLS_G9")
      (libsource (lib "eagle-import") (part "capacitors_CSTLS_G"))
    )
    (comp (ref "R1")
      (value "510R")
      (footprint "eagle-import:RESISTOR_7.5")
      (libsource (lib "eagle-import") (part "RESISTORRESISTOR/UPRIGHT/7.5"))
    )
    (comp (ref "R2")
      (value "510R")
      (footprint "eagle-import:RESISTOR_7.5")
      (libsource (lib "eagle-import") (part "RESISTORRESISTOR/UPRIGHT/7.5"))
    )
    (comp (ref "R3")
      (value "510R")
      (footprint "eagle-import:RESISTOR_7.5")
      (libsource (lib "eagle-import") (part "RESISTORRESISTOR/UPRIGHT/7.5"))
    )
    (comp (ref "R4")
      (value "510R")
      (footprint "eagle-import:RESISTOR_7.5")
      (libsource (lib "eagle-import") (part "RESISTORRESISTOR/UPRIGHT/7.5"))
    )
    (comp (ref "R5")
      (value "510R")
      (footprint "eagle-import:RESISTOR_7.5")
      (libsource (lib "eagle-import") (part "RESISTORRESISTOR/UPRIGHT/7.5"))
    )
    (comp (ref "R6")
      (value "510R")
      (footprint "eagle-import:RESISTOR_7.5")
      (libsource (lib "eagle-import") (part "RESISTORRESISTOR/UPRIGHT/7.5"))
    )
    (comp (ref "R7")
      (value "510R")
      (footprint "eagle-import:RESISTOR_7.5")
      (libsource (lib "eagle-import") (part "RESISTORRESISTOR/UPRIGHT/7.5"))
    )
    (comp (ref "R8")
      (value "510R")
      (footprint "eagle-import:RESISTOR_7.5")
      (libsource (lib "eagle-import") (part "RESISTORRESISTOR/UPRIGHT/7.5"))
    )
    (comp (ref "R9")
      (value "510R")
      (footprint "eagle-import:RESISTOR_7.5")
      (libsource (lib "eagle-import") (part "RESISTORRESISTOR/UPRIGHT/7.5"))
    )
    (comp (ref "R10")
      (value "510R")
      (footprint "eagle-import:RESISTOR_7.5")
      (libsource (lib "eagle-import") (part "RESISTORRESISTOR/UPRIGHT/7.5"))
    )
    (comp (ref "R11")
      (value "510R")
      (footprint "eagle-import:RESISTOR_7.5")
      (libsource (lib "eagle-import") (part "RESISTORRESISTOR/UPRIGHT/7.5"))
    )
    (comp (ref "R12")
      (value "510R")
      (footprint "eagle-import:RESISTOR_7.5")
      (libsource (lib "eagle-import") (part "RESISTORRESISTOR/UPRIGHT/7.5"))
    )
    (comp (ref "R13")
      (value "1k")
      (footprint "eagle-import:RESISTOR_7.5")
      (libsource (lib "eagle-import") (part "RESISTORRESISTOR/UPRIGHT/7.5"))
    )
    (comp (ref "R14")
      (value "1k")
      (footprint "eagle-import:RESISTOR_7.5")
      (libsource (lib "eagle-import") (part "RESISTORRESISTOR/UPRIGHT/7.5"))
    )
    (comp (ref "R15")
      (value "1k")
      (footprint "eagle-import:RESISTOR_7.5")
      (libsource (lib "eagle-import") (part "RESISTORRESISTOR/UPRIGHT/7.5"))
    )
    (comp (ref "R16")
      (value "1k")
      (footprint "eagle-import:RESISTOR_7.5")
      (libsource (lib "eagle-import") (part "RESISTORRESISTOR/UPRIGHT/7.5"))
    )
    (comp (ref "R17")
      (value "1k")
      (footprint "eagle-import:RESISTOR_7.5")
      (libsource (lib "eagle-import") (part "RESISTORRESISTOR/UPRIGHT/7.5"))
    )
    (comp (ref "R18")
      (value "1k")
      (footprint "eagle-import:RESISTOR_7.5")
      (libsource (lib "eagle-import") (part "RESISTORRESISTOR/UPRIGHT/7.5"))
    )
    (comp (ref "RX")
      (value "HEADER/MALE/01")
      (footprint "eagle-import:HEADER_MALE_01")
      (fields (field (name "SPICEPREFIX") "X"))
      (libsource (lib "eagle-import") (part "HEADER/MALE/01"))
    )
    (comp (ref "STK_3.3V")
      (value "HEADER/MALE/01")
      (footprint "eagle-import:HEADER_MALE_01")
      (fields (field (name "SPICEPREFIX") "X"))
      (libsource (lib "eagle-import") (part "HEADER/MALE/01"))
    )
    (comp (ref "STK_BTN")
      (value "HEADER/MALE/01")
      (footprint "eagle-import:HEADER_MALE_01")
      (fields (field (name "SPICEPREFIX") "X"))
      (libsource (lib "eagle-import") (part "HEADER/MALE/01"))
    )
    (comp (ref "STK_GND")
      (value "HEADER/MALE/01")
      (footprint "eagle-import:HEADER_MALE_01")
      (fields (field (name "SPICEPREFIX") "X"))
      (libsource (lib "eagle-import") (part "HEADER/MALE/01"))
    )
    (comp (ref "STK_X")
      (value "HEADER/MALE/01")
      (footprint "eagle-import:HEADER_MALE_01")
      (fields (field (name "SPICEPREFIX") "X"))
      (libsource (lib "eagle-import") (part "HEADER/MALE/01"))
    )
    (comp (ref "STK_Y")
      (value "HEADER/MALE/01")
      (footprint "eagle-import:HEADER_MALE_01")
      (fields (field (name "SPICEPREFIX") "X"))
      (libsource (lib "eagle-import") (part "HEADER/MALE/01"))
    )
    (comp (ref "TX")
      (value "HEADER/MALE/01")
      (footprint "eagle-import:HEADER_MALE_01")
      (fields (field (name "SPICEPREFIX") "X"))
      (libsource (lib "eagle-import") (part "HEADER/MALE/01"))
    )
    (comp (ref "U$1")
      (value "TEENSY41-E")
      (footprint "eagle-import:TENNSY41-E")
      (libsource (lib "eagle-import") (part "TEENSY41-E"))
    )
  )
  (nets
    (net (code "1") (name "+5V") (class "Default")
      (node (ref "5V") (pin "1") (pinfunction "3_1") (pintype "passive"))
      (node (ref "5V1") (pin "1") (pinfunction "3_1") (pintype "passive"))
      (node (ref "5V2") (pin "1") (pinfunction "3_1") (pintype "passive"))
      (node (ref "C3") (pin "+") (pinfunction "+_+") (pintype "passive"))
      (node (ref "IC1") (pin "20") (pinfunction "AVCC_20") (pintype "bidirectional"))
      (node (ref "IC1") (pin "7") (pinfunction "VCC_7") (pintype "bidirectional"))
      (node (ref "IC2") (pin "3") (pinfunction "VO_3") (pintype "passive"))
      (node (ref "LED_VCC") (pin "1") (pinfunction "3_1") (pintype "passive"))
      (node (ref "MTX_5V") (pin "1") (pinfunction "3_1") (pintype "passive"))
      (node (ref "U$1") (pin "VIN") (pinfunction "VIN_VIN") (pintype "bidirectional"))
    )
    (net (code "2") (name "+12V") (class "Default")
      (node (ref "+12V1") (pin "1") (pinfunction "3_1") (pintype "passive"))
      (node (ref "+12V2") (pin "1") (pinfunction "3_1") (pintype "passive"))
      (node (ref "+V") (pin "1") (pinfunction "3_1") (pintype "passive"))
      (node (ref "+V2") (pin "1") (pinfunction "3_1") (pintype "passive"))
      (node (ref "+V3") (pin "1") (pinfunction "3_1") (pintype "passive"))
      (node (ref "C1") (pin "+") (pinfunction "+_+") (pintype "passive"))
      (node (ref "IC2") (pin "1") (pinfunction "VI_1") (pintype "input"))
    )
    (net (code "3") (name "-12V") (class "Default")
      (node (ref "-12V1") (pin "1") (pinfunction "3_1") (pintype "passive"))
      (node (ref "-12V2") (pin "1") (pinfunction "3_1") (pintype "passive"))
      (node (ref "-V") (pin "1") (pinfunction "3_1") (pintype "passive"))
      (node (ref "-V2") (pin "1") (pinfunction "3_1") (pintype "passive"))
      (node (ref "-V3") (pin "1") (pinfunction "3_1") (pintype "passive"))
      (node (ref "C2") (pin "-") (pinfunction "-_-") (pintype "passive"))
    )
    (net (code "4") (name "/3.3V") (class "Default")
      (node (ref "3.3V") (pin "1") (pinfunction "3_1") (pintype "passive"))
      (node (ref "OLED_3.3V") (pin "1") (pinfunction "3_1") (pintype "passive"))
      (node (ref "STK_3.3V") (pin "1") (pinfunction "3_1") (pintype "passive"))
      (node (ref "U$1") (pin "3V3-1") (pinfunction "3V3-1_3V3-1") (pintype "bidirectional"))
      (node (ref "U$1") (pin "3V3-3") (pinfunction "3V3-3_3V3-3") (pintype "bidirectional"))
    )
    (net (code "5") (name "/LED_DATA") (class "Default")
      (node (ref "IC1") (pin "2") (pinfunction "(PCI16/RXD)PD0_2") (pintype "bidirectional"))
      (node (ref "U$1") (pin "35-TX8") (pinfunction "35/TX8_35-TX8") (pintype "bidirectional"))
    )
    (net (code "6") (name "GND") (class "Default")
      (node (ref "C1") (pin "-") (pinfunction "-_-") (pintype "passive"))
      (node (ref "C2") (pin "+") (pinfunction "+_+") (pintype "passive"))
      (node (ref "C3") (pin "-") (pinfunction "-_-") (pintype "passive"))
      (node (ref "ENC_BTN_GND") (pin "1") (pinfunction "3_1") (pintype "passive"))
      (node (ref "ENC_GND") (pin "1") (pinfunction "3_1") (pintype "passive"))
      (node (ref "GND") (pin "1") (pinfunction "3_1") (pintype "passive"))
      (node (ref "GND1") (pin "1") (pinfunction "3_1") (pintype "passive"))
      (node (ref "GND2") (pin "1") (pinfunction "3_1") (pintype "passive"))
      (node (ref "GND3") (pin "1") (pinfunction "3_1") (pintype "passive"))
      (node (ref "GND4") (pin "1") (pinfunction "3_1") (pintype "passive"))
      (node (ref "GND5") (pin "1") (pinfunction "3_1") (pintype "passive"))
      (node (ref "GND6") (pin "1") (pinfunction "3_1") (pintype "passive"))
      (node (ref "GND7") (pin "1") (pinfunction "3_1") (pintype "passive"))
      (node (ref "GND8") (pin "1") (pinfunction "3_1") (pintype "passive"))
      (node (ref "IC1") (pin "22") (pinfunction "AGND_22") (pintype "bidirectional"))
      (node (ref "IC1") (pin "8") (pinfunction "GND_8") (pintype "bidirectional"))
      (node (ref "IC2") (pin "2") (pinfunction "GND_2") (pintype "passive"))
      (node (ref "LED_GND") (pin "1") (pinfunction "3_1") (pintype "passive"))
      (node (ref "MTX_GND") (pin "1") (pinfunction "3_1") (pintype "passive"))
      (node (ref "OLED_GND") (pin "1") (pinfunction "3_1") (pintype "passive"))
      (node (ref "Q1") (pin "3") (pinfunction "E_3") (pintype "passive"))
      (node (ref "Q2") (pin "3") (pinfunction "E_3") (pintype "passive"))
      (node (ref "Q3") (pin "3") (pinfunction "E_3") (pintype "passive"))
      (node (ref "Q4") (pin "3") (pinfunction "E_3") (pintype "passive"))
      (node (ref "Q5") (pin "3") (pinfunction "E_3") (pintype "passive"))
      (node (ref "Q6") (pin "3") (pinfunction "E_3") (pintype "passive"))
      (node (ref "Q7") (pin "2") (pinfunction "VSS_2") (pintype "power_in"))
      (node (ref "STK_GND") (pin "1") (pinfunction "3_1") (pintype "passive"))
      (node (ref "U$1") (pin "GND1") (pinfunction "GND1_GND1") (pintype "bidirectional"))
      (node (ref "U$1") (pin "GND3") (pinfunction "GND3_GND3") (pintype "bidirectional"))
      (node (ref "U$1") (pin "GND6") (pinfunction "GND6_GND6") (pintype "bidirectional"))
    )
    (net (code "7") (name "Net-(7-3)") (class "Default")
      (node (ref "7") (pin "1") (pinfunction "3_1") (pintype "passive"))
      (node (ref "U$1") (pin "7-RX2/OUT1A") (pinfunction "7-RX2/OUT1A_7-RX2/OUT1A") (pintype "bidirectional"))
    )
    (net (code "8") (name "Net-(8-3)") (class "Default")
      (node (ref "8") (pin "1") (pinfunction "3_1") (pintype "passive"))
      (node (ref "U$1") (pin "8-TX2/IN1") (pinfunction "8-TX2/IN1_8-TX2/IN1") (pintype "bidirectional"))
    )
    (net (code "9") (name "Net-(14-3)") (class "Default")
      (node (ref "14") (pin "1") (pinfunction "3_1") (pintype "passive"))
      (node (ref "U$1") (pin "14-A0/TX3/SPDIF_OUT") (pinfunction "14-A0/TX3/SPDIF_OUT_14-A0/TX3/SPDIF_OUT") (pintype "bidirectional"))
    )
    (net (code "10") (name "Net-(15-3)") (class "Default")
      (node (ref "15") (pin "1") (pinfunction "3_1") (pintype "passive"))
      (node (ref "U$1") (pin "15-A1/RX3/SPDIF_IN") (pinfunction "15-A1/RX3/SPDIF_IN_15-A1/RX3/SPDIF_IN") (pintype "bidirectional"))
    )
    (net (code "11") (name "Net-(16-3)") (class "Default")
      (node (ref "16") (pin "1") (pinfunction "3_1") (pintype "passive"))
      (node (ref "U$1") (pin "16-A2/RX4/SCL1") (pinfunction "16-A2/RX4/SCL1_16-A2/RX4/SCL1") (pintype "bidirectional"))
    )
    (net (code "12") (name "Net-(17-3)") (class "Default")
      (node (ref "17") (pin "1") (pinfunction "3_1") (pintype "passive"))
      (node (ref "U$1") (pin "17-A3/TX4/SDA1") (pinfunction "17-A3/TX4/SDA1_17-A3/TX4/SDA1") (pintype "bidirectional"))
    )
    (net (code "13") (name "Net-(20-3)") (class "Default")
      (node (ref "20") (pin "1") (pinfunction "3_1") (pintype "passive"))
      (node (ref "U$1") (pin "20-A6/TX5/LRCLK1") (pinfunction "20-A6/TX5/LRCLK1_20-A6/TX5/LRCLK1") (pintype "bidirectional"))
    )
    (net (code "14") (name "Net-(21-3)") (class "Default")
      (node (ref "21") (pin "1") (pinfunction "3_1") (pintype "passive"))
      (node (ref "U$1") (pin "21-A7/RX5/BCLK1") (pinfunction "21-A7/RX5/BCLK1_21-A7/RX5/BCLK1") (pintype "bidirectional"))
    )
    (net (code "15") (name "Net-(36-3)") (class "Default")
      (node (ref "36") (pin "1") (pinfunction "3_1") (pintype "passive"))
      (node (ref "U$1") (pin "36-PWM") (pinfunction "36-PWM_36-PWM") (pintype "bidirectional"))
    )
    (net (code "16") (name "Net-(37-3)") (class "Default")
      (node (ref "37") (pin "1") (pinfunction "3_1") (pintype "passive"))
      (node (ref "U$1") (pin "37-PWM") (pinfunction "37-PWM_37-PWM") (pintype "bidirectional"))
    )
    (net (code "17") (name "Net-(38-3)") (class "Default")
      (node (ref "38") (pin "1") (pinfunction "3_1") (pintype "passive"))
      (node (ref "U$1") (pin "38-A14/CS/IN1") (pinfunction "38-A14/CS/IN1_38-A14/CS/IN1") (pintype "bidirectional"))
    )
    (net (code "18") (name "Net-(39-3)") (class "Default")
      (node (ref "39") (pin "1") (pinfunction "3_1") (pintype "passive"))
      (node (ref "U$1") (pin "39-A15/CS/OUT1A") (pinfunction "39-A15/CS/OUT1A_39-A15/CS/OUT1A") (pintype "bidirectional"))
    )
    (net (code "19") (name "Net-(40-3)") (class "Default")
      (node (ref "40") (pin "1") (pinfunction "3_1") (pintype "passive"))
      (node (ref "U$1") (pin "40-A16/CS1") (pinfunction "40-A16/CS1_40-A16/CS1") (pintype "bidirectional"))
    )
    (net (code "20") (name "Net-(41-3)") (class "Default")
      (node (ref "41") (pin "1") (pinfunction "3_1") (pintype "passive"))
      (node (ref "U$1") (pin "41-A17/MISO1") (pinfunction "41-A17/MISO1_41-A17/MISO1") (pintype "bidirectional"))
    )
    (net (code "21") (name "Net-(ENC_1-3)") (class "Default")
      (node (ref "ENC_1") (pin "1") (pinfunction "3_1") (pintype "passive"))
      (node (ref "U$1") (pin "3-LRCLK2") (pinfunction "3-LRCLK2_3-LRCLK2") (pintype "bidirectional"))
    )
    (net (code "22") (name "Net-(ENC_2-3)") (class "Default")
      (node (ref "ENC_2") (pin "1") (pinfunction "3_1") (pintype "passive"))
      (node (ref "U$1") (pin "4-BCLK2") (pinfunction "4-BCLK2_4-BCLK2") (pintype "bidirectional"))
    )
    (net (code "23") (name "Net-(ENC_BTN-3)") (class "Default")
      (node (ref "ENC_BTN") (pin "1") (pinfunction "3_1") (pintype "passive"))
      (node (ref "U$1") (pin "5-IN2") (pinfunction "5-IN2_5-IN2") (pintype "bidirectional"))
    )
    (net (code "24") (name "Net-(IC1-(PCI0{slash}ICP{slash}CLKO)PB0)") (class "Default")
      (node (ref "IC1") (pin "14") (pinfunction "(PCI0/ICP/CLKO)PB0_14") (pintype "bidirectional"))
      (node (ref "R7") (pin "1") (pinfunction "1_1") (pintype "passive"))
    )
    (net (code "25") (name "Net-(IC1-(PCI1{slash}OC1A{slash}OC1S)PB1)") (class "Default")
      (node (ref "IC1") (pin "15") (pinfunction "(PCI1/OC1A/OC1S)PB1_15") (pintype "bidirectional"))
      (node (ref "R8") (pin "1") (pinfunction "1_1") (pintype "passive"))
    )
    (net (code "26") (name "Net-(IC1-(PCI2{slash}SS{slash}OC1B)PB2)") (class "Default")
      (node (ref "IC1") (pin "16") (pinfunction "(PCI2/SS/OC1B)PB2_16") (pintype "bidirectional"))
      (node (ref "R9") (pin "1") (pinfunction "1_1") (pintype "passive"))
    )
    (net (code "27") (name "Net-(IC1-(PCI3{slash}MOSI{slash}OC2A)PB3)") (class "Default")
      (node (ref "IC1") (pin "17") (pinfunction "(PCI3/MOSI/OC2A)PB3_17") (pintype "bidirectional"))
      (node (ref "LED_MOSI") (pin "1") (pinfunction "3_1") (pintype "passive"))
      (node (ref "R10") (pin "1") (pinfunction "1_1") (pintype "passive"))
    )
    (net (code "28") (name "Net-(IC1-(PCI4{slash}MISO)PB4)") (class "Default")
      (node (ref "IC1") (pin "18") (pinfunction "(PCI4/MISO)PB4_18") (pintype "bidirectional"))
      (node (ref "LED_MISO") (pin "1") (pinfunction "3_1") (pintype "passive"))
      (node (ref "R11") (pin "1") (pinfunction "1_1") (pintype "passive"))
    )
    (net (code "29") (name "Net-(IC1-(PCI5{slash}SCK)PB5)") (class "Default")
      (node (ref "IC1") (pin "19") (pinfunction "(PCI5/SCK)PB5_19") (pintype "bidirectional"))
      (node (ref "LED_SCK") (pin "1") (pinfunction "3_1") (pintype "passive"))
      (node (ref "R12") (pin "1") (pinfunction "1_1") (pintype "passive"))
    )
    (net (code "30") (name "Net-(IC1-(PCI8{slash}ADC0)PC0)") (class "Default")
      (node (ref "IC1") (pin "23") (pinfunction "(PCI8/ADC0)PC0_23") (pintype "bidirectional"))
      (node (ref "R18") (pin "1") (pinfunction "1_1") (pintype "passive"))
    )
    (net (code "31") (name "Net-(IC1-(PCI9{slash}ADC1)PC1)") (class "Default")
      (node (ref "IC1") (pin "24") (pinfunction "(PCI9/ADC1)PC1_24") (pintype "bidirectional"))
      (node (ref "R17") (pin "1") (pinfunction "1_1") (pintype "passive"))
    )
    (net (code "32") (name "Net-(IC1-(PCI10{slash}ADC2)PC2)") (class "Default")
      (node (ref "IC1") (pin "25") (pinfunction "(PCI10/ADC2)PC2_25") (pintype "bidirectional"))
      (node (ref "R16") (pin "1") (pinfunction "1_1") (pintype "passive"))
    )
    (net (code "33") (name "Net-(IC1-(PCI11{slash}ADC3)PC3)") (class "Default")
      (node (ref "IC1") (pin "26") (pinfunction "(PCI11/ADC3)PC3_26") (pintype "bidirectional"))
      (node (ref "R15") (pin "1") (pinfunction "1_1") (pintype "passive"))
    )
    (net (code "34") (name "Net-(IC1-(PCI12{slash}ADC4{slash}SDA)PC4)") (class "Default")
      (node (ref "IC1") (pin "27") (pinfunction "(PCI12/ADC4/SDA)PC4_27") (pintype "bidirectional"))
      (node (ref "R14") (pin "1") (pinfunction "1_1") (pintype "passive"))
    )
    (net (code "35") (name "Net-(IC1-(PCI13{slash}ADC5{slash}SCL)PC5)") (class "Default")
      (node (ref "IC1") (pin "28") (pinfunction "(PCI13/ADC5/SCL)PC5_28") (pintype "bidirectional"))
      (node (ref "R13") (pin "1") (pinfunction "1_1") (pintype "passive"))
    )
    (net (code "36") (name "Net-(IC1-(PCI18{slash}INT0)PD2)") (class "Default")
      (node (ref "IC1") (pin "4") (pinfunction "(PCI18/INT0)PD2_4") (pintype "bidirectional"))
      (node (ref "R1") (pin "1") (pinfunction "1_1") (pintype "passive"))
    )
    (net (code "37") (name "Net-(IC1-(PCI19{slash}INT1{slash}OC2B)PD3)") (class "Default")
      (node (ref "IC1") (pin "5") (pinfunction "(PCI19/INT1/OC2B)PD3_5") (pintype "bidirectional"))
      (node (ref "R2") (pin "1") (pinfunction "1_1") (pintype "passive"))
    )
    (net (code "38") (name "Net-(IC1-(PCI20{slash}XCK{slash}T0)PD4)") (class "Default")
      (node (ref "IC1") (pin "6") (pinfunction "(PCI20/XCK/T0)PD4_6") (pintype "bidirectional"))
      (node (ref "R3") (pin "1") (pinfunction "1_1") (pintype "passive"))
    )
    (net (code "39") (name "Net-(IC1-(PCI21{slash}T1{slash}OC0B)PD5)") (class "Default")
      (node (ref "IC1") (pin "11") (pinfunction "(PCI21/T1/OC0B)PD5_11") (pintype "bidirectional"))
      (node (ref "R4") (pin "1") (pinfunction "1_1") (pintype "passive"))
    )
    (net (code "40") (name "Net-(IC1-(PCI22{slash}AIN0OC0A)PD6)") (class "Default")
      (node (ref "IC1") (pin "12") (pinfunction "(PCI22/AIN0OC0A)PD6_12") (pintype "bidirectional"))
      (node (ref "R5") (pin "1") (pinfunction "1_1") (pintype "passive"))
    )
    (net (code "41") (name "Net-(IC1-(PCI23{slash}AIN1)PD7)") (class "Default")
      (node (ref "IC1") (pin "13") (pinfunction "(PCI23/AIN1)PD7_13") (pintype "bidirectional"))
      (node (ref "R6") (pin "1") (pinfunction "1_1") (pintype "passive"))
    )
    (net (code "42") (name "Net-(IC1-PB6(XTAL1{slash}TOSC1{slash}PCI6))") (class "Default")
      (node (ref "IC1") (pin "9") (pinfunction "PB6(XTAL1/TOSC1/PCI6)_9") (pintype "bidirectional"))
      (node (ref "Q7") (pin "1") (pinfunction "1_1") (pintype "output"))
    )
    (net (code "43") (name "Net-(IC1-PB7(XTAL2{slash}TOSC2{slash}PCI7))") (class "Default")
      (node (ref "IC1") (pin "10") (pinfunction "PB7(XTAL2/TOSC2/PCI7)_10") (pintype "bidirectional"))
      (node (ref "Q7") (pin "3") (pinfunction "3_3") (pintype "input"))
    )
    (net (code "44") (name "Net-(IC1-PC6({slash}RESET{slash}PCI14))") (class "Default")
      (node (ref "IC1") (pin "1") (pinfunction "PC6(/RESET/PCI14)_1") (pintype "bidirectional"))
      (node (ref "LED_RST") (pin "1") (pinfunction "3_1") (pintype "passive"))
    )
    (net (code "45") (name "Net-(KEY_X1-3)") (class "Default")
      (node (ref "KEY_X1") (pin "1") (pinfunction "3_1") (pintype "passive"))
      (node (ref "U$1") (pin "24-A10/TX6/SCL2") (pinfunction "24-A10/TX6/SCL2_24-A10/TX6/SCL2") (pintype "bidirectional"))
    )
    (net (code "46") (name "Net-(KEY_X2-3)") (class "Default")
      (node (ref "KEY_X2") (pin "1") (pinfunction "3_1") (pintype "passive"))
      (node (ref "U$1") (pin "25-A11/RX6/SDA2") (pinfunction "25-A11/RX6/SDA2_25-A11/RX6/SDA2") (pintype "bidirectional"))
    )
    (net (code "47") (name "Net-(KEY_X3-3)") (class "Default")
      (node (ref "KEY_X3") (pin "1") (pinfunction "3_1") (pintype "passive"))
      (node (ref "U$1") (pin "26-A12/MOSI1") (pinfunction "26-A12/MOSI1_26-A12/MOSI1") (pintype "bidirectional"))
    )
    (net (code "48") (name "Net-(KEY_X4-3)") (class "Default")
      (node (ref "KEY_X4") (pin "1") (pinfunction "3_1") (pintype "passive"))
      (node (ref "U$1") (pin "27-A13/SCK1") (pinfunction "27-A13/SCK1_27-A13/SCK1") (pintype "bidirectional"))
    )
    (net (code "49") (name "Net-(KEY_Y1-3)") (class "Default")
      (node (ref "KEY_Y1") (pin "1") (pinfunction "3_1") (pintype "passive"))
      (node (ref "U$1") (pin "28-RX7") (pinfunction "28-RX7_28-RX7") (pintype "bidirectional"))
    )
    (net (code "50") (name "Net-(KEY_Y2-3)") (class "Default")
      (node (ref "KEY_Y2") (pin "1") (pinfunction "3_1") (pintype "passive"))
      (node (ref "U$1") (pin "29-TX7") (pinfunction "29-TX7_29-TX7") (pintype "bidirectional"))
    )
    (net (code "51") (name "Net-(KEY_Y3-3)") (class "Default")
      (node (ref "KEY_Y3") (pin "1") (pinfunction "3_1") (pintype "passive"))
      (node (ref "U$1") (pin "30-CRX3") (pinfunction "30-CRX3_30-CRX3") (pintype "bidirectional"))
    )
    (net (code "52") (name "Net-(KEY_Y4-3)") (class "Default")
      (node (ref "KEY_Y4") (pin "1") (pinfunction "3_1") (pintype "passive"))
      (node (ref "U$1") (pin "31-CTX3") (pinfunction "31-CTX3_31-CTX3") (pintype "bidirectional"))
    )
    (net (code "53") (name "Net-(KEY_Y5-3)") (class "Default")
      (node (ref "KEY_Y5") (pin "1") (pinfunction "3_1") (pintype "passive"))
      (node (ref "U$1") (pin "32-OUT1B") (pinfunction "32-OUT1B_32-OUT1B") (pintype "bidirectional"))
    )
    (net (code "54") (name "Net-(KEY_Y6-3)") (class "Default")
      (node (ref "KEY_Y6") (pin "1") (pinfunction "3_1") (pintype "passive"))
      (node (ref "U$1") (pin "33-MCLK2") (pinfunction "33-MCLK2_33-MCLK2") (pintype "bidirectional"))
    )
    (net (code "55") (name "Net-(LED_B1-3)") (class "Default")
      (node (ref "LED_B1") (pin "1") (pinfunction "3_1") (pintype "passive"))
      (node (ref "LED_B13") (pin "1") (pinfunction "3_1") (pintype "passive"))
      (node (ref "LED_B17") (pin "1") (pinfunction "3_1") (pintype "passive"))
      (node (ref "LED_B21") (pin "1") (pinfunction "3_1") (pintype "passive"))
      (node (ref "LED_B5") (pin "1") (pinfunction "3_1") (pintype "passive"))
      (node (ref "LED_B9") (pin "1") (pinfunction "3_1") (pintype "passive"))
      (node (ref "R3") (pin "2") (pinfunction "2_2") (pintype "passive"))
    )
    (net (code "56") (name "Net-(LED_B10-3)") (class "Default")
      (node (ref "LED_B10") (pin "1") (pinfunction "3_1") (pintype "passive"))
      (node (ref "LED_B14") (pin "1") (pinfunction "3_1") (pintype "passive"))
      (node (ref "LED_B18") (pin "1") (pinfunction "3_1") (pintype "passive"))
      (node (ref "LED_B2") (pin "1") (pinfunction "3_1") (pintype "passive"))
      (node (ref "LED_B22") (pin "1") (pinfunction "3_1") (pintype "passive"))
      (node (ref "LED_B6") (pin "1") (pinfunction "3_1") (pintype "passive"))
      (node (ref "R6") (pin "2") (pinfunction "2_2") (pintype "passive"))
    )
    (net (code "57") (name "Net-(LED_B11-3)") (class "Default")
      (node (ref "LED_B11") (pin "1") (pinfunction "3_1") (pintype "passive"))
      (node (ref "LED_B15") (pin "1") (pinfunction "3_1") (pintype "passive"))
      (node (ref "LED_B19") (pin "1") (pinfunction "3_1") (pintype "passive"))
      (node (ref "LED_B23") (pin "1") (pinfunction "3_1") (pintype "passive"))
      (node (ref "LED_B3") (pin "1") (pinfunction "3_1") (pintype "passive"))
      (node (ref "LED_B7") (pin "1") (pinfunction "3_1") (pintype "passive"))
      (node (ref "R9") (pin "2") (pinfunction "2_2") (pintype "passive"))
    )
    (net (code "58") (name "Net-(LED_B12-3)") (class "Default")
      (node (ref "LED_B12") (pin "1") (pinfunction "3_1") (pintype "passive"))
      (node (ref "LED_B16") (pin "1") (pinfunction "3_1") (pintype "passive"))
      (node (ref "LED_B20") (pin "1") (pinfunction "3_1") (pintype "passive"))
      (node (ref "LED_B24") (pin "1") (pinfunction "3_1") (pintype "passive"))
      (node (ref "LED_B4") (pin "1") (pinfunction "3_1") (pintype "passive"))
      (node (ref "LED_B8") (pin "1") (pinfunction "3_1") (pintype "passive"))
      (node (ref "R12") (pin "2") (pinfunction "2_2") (pintype "passive"))
    )
    (net (code "59") (name "Net-(LED_C1-3)") (class "Default")
      (node (ref "LED_C1") (pin "1") (pinfunction "3_1") (pintype "passive"))
      (node (ref "Q6") (pin "1") (pinfunction "C_1") (pintype "passive"))
    )
    (net (code "60") (name "Net-(LED_C2-3)") (class "Default")
      (node (ref "LED_C2") (pin "1") (pinfunction "3_1") (pintype "passive"))
      (node (ref "Q5") (pin "1") (pinfunction "C_1") (pintype "passive"))
    )
    (net (code "61") (name "Net-(LED_C3-3)") (class "Default")
      (node (ref "LED_C3") (pin "1") (pinfunction "3_1") (pintype "passive"))
      (node (ref "Q4") (pin "1") (pinfunction "C_1") (pintype "passive"))
    )
    (net (code "62") (name "Net-(LED_C4-3)") (class "Default")
      (node (ref "LED_C4") (pin "1") (pinfunction "3_1") (pintype "passive"))
      (node (ref "Q3") (pin "1") (pinfunction "C_1") (pintype "passive"))
    )
    (net (code "63") (name "Net-(LED_C5-3)") (class "Default")
      (node (ref "LED_C5") (pin "1") (pinfunction "3_1") (pintype "passive"))
      (node (ref "Q2") (pin "1") (pinfunction "C_1") (pintype "passive"))
    )
    (net (code "64") (name "Net-(LED_C6-3)") (class "Default")
      (node (ref "LED_C6") (pin "1") (pinfunction "3_1") (pintype "passive"))
      (node (ref "Q1") (pin "1") (pinfunction "C_1") (pintype "passive"))
    )
    (net (code "65") (name "Net-(LED_G1-3)") (class "Default")
      (node (ref "LED_G1") (pin "1") (pinfunction "3_1") (pintype "passive"))
      (node (ref "LED_G13") (pin "1") (pinfunction "3_1") (pintype "passive"))
      (node (ref "LED_G17") (pin "1") (pinfunction "3_1") (pintype "passive"))
      (node (ref "LED_G21") (pin "1") (pinfunction "3_1") (pintype "passive"))
      (node (ref "LED_G5") (pin "1") (pinfunction "3_1") (pintype "passive"))
      (node (ref "LED_G9") (pin "1") (pinfunction "3_1") (pintype "passive"))
      (node (ref "R2") (pin "2") (pinfunction "2_2") (pintype "passive"))
    )
    (net (code "66") (name "Net-(LED_G10-3)") (class "Default")
      (node (ref "LED_G10") (pin "1") (pinfunction "3_1") (pintype "passive"))
      (node (ref "LED_G14") (pin "1") (pinfunction "3_1") (pintype "passive"))
      (node (ref "LED_G18") (pin "1") (pinfunction "3_1") (pintype "passive"))
      (node (ref "LED_G2") (pin "1") (pinfunction "3_1") (pintype "passive"))
      (node (ref "LED_G22") (pin "1") (pinfunction "3_1") (pintype "passive"))
      (node (ref "LED_G6") (pin "1") (pinfunction "3_1") (pintype "passive"))
      (node (ref "R5") (pin "2") (pinfunction "2_2") (pintype "passive"))
    )
    (net (code "67") (name "Net-(LED_G11-3)") (class "Default")
      (node (ref "LED_G11") (pin "1") (pinfunction "3_1") (pintype "passive"))
      (node (ref "LED_G15") (pin "1") (pinfunction "3_1") (pintype "passive"))
      (node (ref "LED_G19") (pin "1") (pinfunction "3_1") (pintype "passive"))
      (node (ref "LED_G23") (pin "1") (pinfunction "3_1") (pintype "passive"))
      (node (ref "LED_G3") (pin "1") (pinfunction "3_1") (pintype "passive"))
      (node (ref "LED_G7") (pin "1") (pinfunction "3_1") (pintype "passive"))
      (node (ref "R8") (pin "2") (pinfunction "2_2") (pintype "passive"))
    )
    (net (code "68") (name "Net-(LED_G12-3)") (class "Default")
      (node (ref "LED_G12") (pin "1") (pinfunction "3_1") (pintype "passive"))
      (node (ref "LED_G16") (pin "1") (pinfunction "3_1") (pintype "passive"))
      (node (ref "LED_G20") (pin "1") (pinfunction "3_1") (pintype "passive"))
      (node (ref "LED_G24") (pin "1") (pinfunction "3_1") (pintype "passive"))
      (node (ref "LED_G4") (pin "1") (pinfunction "3_1") (pintype "passive"))
      (node (ref "LED_G8") (pin "1") (pinfunction "3_1") (pintype "passive"))
      (node (ref "R11") (pin "2") (pinfunction "2_2") (pintype "passive"))
    )
    (net (code "69") (name "Net-(LED_R1-3)") (class "Default")
      (node (ref "LED_R1") (pin "1") (pinfunction "3_1") (pintype "passive"))
      (node (ref "LED_R13") (pin "1") (pinfunction "3_1") (pintype "passive"))
      (node (ref "LED_R17") (pin "1") (pinfunction "3_1") (pintype "passive"))
      (node (ref "LED_R21") (pin "1") (pinfunction "3_1") (pintype "passive"))
      (node (ref "LED_R5") (pin "1") (pinfunction "3_1") (pintype "passive"))
      (node (ref "LED_R9") (pin "1") (pinfunction "3_1") (pintype "passive"))
      (node (ref "R1") (pin "2") (pinfunction "2_2") (pintype "passive"))
    )
    (net (code "70") (name "Net-(LED_R10-3)") (class "Default")
      (node (ref "LED_R10") (pin "1") (pinfunction "3_1") (pintype "passive"))
      (node (ref "LED_R14") (pin "1") (pinfunction "3_1") (pintype "passive"))
      (node (ref "LED_R18") (pin "1") (pinfunction "3_1") (pintype "passive"))
      (node (ref "LED_R2") (pin "1") (pinfunction "3_1") (pintype "passive"))
      (node (ref "LED_R22") (pin "1") (pinfunction "3_1") (pintype "passive"))
      (node (ref "LED_R6") (pin "1") (pinfunction "3_1") (pintype "passive"))
      (node (ref "R4") (pin "2") (pinfunction "2_2") (pintype "passive"))
    )
    (net (code "71") (name "Net-(LED_R11-3)") (class "Default")
      (node (ref "LED_R11") (pin "1") (pinfunction "3_1") (pintype "passive"))
      (node (ref "LED_R15") (pin "1") (pinfunction "3_1") (pintype "passive"))
      (node (ref "LED_R19") (pin "1") (pinfunction "3_1") (pintype "passive"))
      (node (ref "LED_R23") (pin "1") (pinfunction "3_1") (pintype "passive"))
      (node (ref "LED_R3") (pin "1") (pinfunction "3_1") (pintype "passive"))
      (node (ref "LED_R7") (pin "1") (pinfunction "3_1") (pintype "passive"))
      (node (ref "R7") (pin "2") (pinfunction "2_2") (pintype "passive"))
    )
    (net (code "72") (name "Net-(LED_R12-3)") (class "Default")
      (node (ref "LED_R12") (pin "1") (pinfunction "3_1") (pintype "passive"))
      (node (ref "LED_R16") (pin "1") (pinfunction "3_1") (pintype "passive"))
      (node (ref "LED_R20") (pin "1") (pinfunction "3_1") (pintype "passive"))
      (node (ref "LED_R24") (pin "1") (pinfunction "3_1") (pintype "passive"))
      (node (ref "LED_R4") (pin "1") (pinfunction "3_1") (pintype "passive"))
      (node (ref "LED_R8") (pin "1") (pinfunction "3_1") (pintype "passive"))
      (node (ref "R10") (pin "2") (pinfunction "2_2") (pintype "passive"))
    )
    (net (code "73") (name "Net-(MTX_CIN-3)") (class "Default")
      (node (ref "MTX_CIN") (pin "1") (pinfunction "3_1") (pintype "passive"))
      (node (ref "U$1") (pin "6-OUT1D") (pinfunction "6-OUT1D_6-OUT1D") (pintype "bidirectional"))
    )
    (net (code "74") (name "Net-(MTX_DIN-3)") (class "Default")
      (node (ref "MTX_DIN") (pin "1") (pinfunction "3_1") (pintype "passive"))
      (node (ref "U$1") (pin "9-OUT1C") (pinfunction "9-OUT1C_9-OUT1C") (pintype "bidirectional"))
    )
    (net (code "75") (name "Net-(OLED_CLK-3)") (class "Default")
      (node (ref "OLED_CLK") (pin "1") (pinfunction "3_1") (pintype "passive"))
      (node (ref "U$1") (pin "13-SCK/LED") (pinfunction "13-SCK/LED_13-SCK/LED") (pintype "bidirectional"))
    )
    (net (code "76") (name "Net-(OLED_CS-3)") (class "Default")
      (node (ref "OLED_CS") (pin "1") (pinfunction "3_1") (pintype "passive"))
      (node (ref "U$1") (pin "10-CS\\MQSR") (pinfunction "10-CS/MQSR_10-CS\\MQSR") (pintype "bidirectional"))
    )
    (net (code "77") (name "Net-(OLED_DC-3)") (class "Default")
      (node (ref "OLED_DC") (pin "1") (pinfunction "3_1") (pintype "passive"))
      (node (ref "U$1") (pin "19-A5/SCL0") (pinfunction "19-A5/SCL0_19-A5/SCL0") (pintype "bidirectional"))
    )
    (net (code "78") (name "Net-(OLED_DIN-3)") (class "Default")
      (node (ref "OLED_DIN") (pin "1") (pinfunction "3_1") (pintype "passive"))
      (node (ref "U$1") (pin "11-MOSI/CTX1") (pinfunction "11-MOSI/CTX1_11-MOSI/CTX1") (pintype "bidirectional"))
    )
    (net (code "79") (name "Net-(OLED_RST-3)") (class "Default")
      (node (ref "OLED_RST") (pin "1") (pinfunction "3_1") (pintype "passive"))
      (node (ref "U$1") (pin "18-A4/SDA0") (pinfunction "18-A4/SDA0_18-A4/SDA0") (pintype "bidirectional"))
    )
    (net (code "80") (name "Net-(Q1-B)") (class "Default")
      (node (ref "Q1") (pin "2") (pinfunction "B_2") (pintype "passive"))
      (node (ref "R13") (pin "2") (pinfunction "2_2") (pintype "passive"))
    )
    (net (code "81") (name "Net-(Q2-B)") (class "Default")
      (node (ref "Q2") (pin "2") (pinfunction "B_2") (pintype "passive"))
      (node (ref "R14") (pin "2") (pinfunction "2_2") (pintype "passive"))
    )
    (net (code "82") (name "Net-(Q3-B)") (class "Default")
      (node (ref "Q3") (pin "2") (pinfunction "B_2") (pintype "passive"))
      (node (ref "R15") (pin "2") (pinfunction "2_2") (pintype "passive"))
    )
    (net (code "83") (name "Net-(Q4-B)") (class "Default")
      (node (ref "Q4") (pin "2") (pinfunction "B_2") (pintype "passive"))
      (node (ref "R16") (pin "2") (pinfunction "2_2") (pintype "passive"))
    )
    (net (code "84") (name "Net-(Q5-B)") (class "Default")
      (node (ref "Q5") (pin "2") (pinfunction "B_2") (pintype "passive"))
      (node (ref "R17") (pin "2") (pinfunction "2_2") (pintype "passive"))
    )
    (net (code "85") (name "Net-(Q6-B)") (class "Default")
      (node (ref "Q6") (pin "2") (pinfunction "B_2") (pintype "passive"))
      (node (ref "R18") (pin "2") (pinfunction "2_2") (pintype "passive"))
    )
    (net (code "86") (name "Net-(RX-3)") (class "Default")
      (node (ref "RX") (pin "1") (pinfunction "3_1") (pintype "passive"))
      (node (ref "U$1") (pin "0-RX1/CS1/CRX2") (pinfunction "0-RX1/CS1/CRX2_0-RX1/CS1/CRX2") (pintype "bidirectional"))
    )
    (net (code "87") (name "Net-(STK_BTN-3)") (class "Default")
      (node (ref "STK_BTN") (pin "1") (pinfunction "3_1") (pintype "passive"))
      (node (ref "U$1") (pin "2-OUT2") (pinfunction "2-OUT2_2-OUT2") (pintype "bidirectional"))
    )
    (net (code "88") (name "Net-(STK_X-3)") (class "Default")
      (node (ref "STK_X") (pin "1") (pinfunction "3_1") (pintype "passive"))
      (node (ref "U$1") (pin "22-A8/CTX1") (pinfunction "22-A8/CTX1_22-A8/CTX1") (pintype "bidirectional"))
    )
    (net (code "89") (name "Net-(STK_Y-3)") (class "Default")
      (node (ref "STK_Y") (pin "1") (pinfunction "3_1") (pintype "passive"))
      (node (ref "U$1") (pin "23-A9/CRX1/MCLK1") (pinfunction "23-A9/CRX1/MCLK1_23-A9/CRX1/MCLK1") (pintype "bidirectional"))
    )
    (net (code "90") (name "Net-(TX-3)") (class "Default")
      (node (ref "TX") (pin "1") (pinfunction "3_1") (pintype "passive"))
      (node (ref "U$1") (pin "1-TX1/MISO1/CTX2") (pinfunction "1-TX1/MISO1/CTX2_1-TX1/MISO1/CTX2") (pintype "bidirectional"))
    )
    (net (code "91") (name "unconnected-(IC1-(PCI17{slash}TXD)PD1-Pad3)") (class "Default")
      (node (ref "IC1") (pin "3") (pinfunction "(PCI17/TXD)PD1_3") (pintype "bidirectional"))
    )
    (net (code "92") (name "unconnected-(IC1-AREF-Pad21)") (class "Default")
      (node (ref "IC1") (pin "21") (pinfunction "AREF_21") (pintype "bidirectional"))
    )
    (net (code "93") (name "unconnected-(U$1-5V-Pad+5V)") (class "Default")
      (node (ref "U$1") (pin "+5V") (pinfunction "5V_+5V") (pintype "bidirectional"))
    )
    (net (code "94") (name "unconnected-(U$1-Pad3V3-2)") (class "Default")
      (node (ref "U$1") (pin "3V3-2") (pinfunction "3V3-2_3V3-2") (pintype "bidirectional"))
    )
    (net (code "95") (name "unconnected-(U$1-Pad12-MISO{slash}MQSL)") (class "Default")
      (node (ref "U$1") (pin "12-MISO/MQSL") (pinfunction "12-MISO/MQSL_12-MISO/MQSL") (pintype "bidirectional"))
    )
    (net (code "96") (name "unconnected-(U$1-Pad34-RX8)") (class "Default")
      (node (ref "U$1") (pin "34-RX8") (pinfunction "34-RX8_34-RX8") (pintype "bidirectional"))
    )
    (net (code "97") (name "unconnected-(U$1-PadDM)") (class "Default")
      (node (ref "U$1") (pin "DM") (pinfunction "DM_DM") (pintype "bidirectional"))
    )
    (net (code "98") (name "unconnected-(U$1-PadDP)") (class "Default")
      (node (ref "U$1") (pin "DP") (pinfunction "DP_DP") (pintype "bidirectional"))
    )
    (net (code "99") (name "unconnected-(U$1-PadGND2)") (class "Default")
      (node (ref "U$1") (pin "GND2") (pinfunction "GND2_GND2") (pintype "bidirectional"))
    )
    (net (code "100") (name "unconnected-(U$1-PadGND4)") (class "Default")
      (node (ref "U$1") (pin "GND4") (pinfunction "GND4_GND4") (pintype "bidirectional"))
    )
    (net (code "101") (name "unconnected-(U$1-PadGND5)") (class "Default")
      (node (ref "U$1") (pin "GND5") (pinfunction "GND5_GND5") (pintype "bidirectional"))
    )
    (net (code "102") (name "unconnected-(U$1-PadON{slash}OFF)") (class "Default")
      (node (ref "U$1") (pin "ON/OFF") (pinfunction "ON/OFF_ON/OFF") (pintype "bidirectional"))
    )
    (net (code "103") (name "unconnected-(U$1-PadPROGRAM)") (class "Default")
      (node (ref "U$1") (pin "PROGRAM") (pinfunction "PROGRAM_PROGRAM") (pintype "bidirectional"))
    )
    (net (code "104") (name "unconnected-(U$1-PadVBAT)") (class "Default")
      (node (ref "U$1") (pin "VBAT") (pinfunction "VBAT_VBAT") (pintype "bidirectional"))
    )
    (net (code "105") (name "unconnected-(U$1-PadVUSB)") (class "Default")
      (node (ref "U$1") (pin "VUSB") (pinfunction "VUSB_VUSB") (pintype "bidirectional"))
    )
  )
)
